# MSXII_SteeringWheelLeftBoard.net
KiCad netlist of a schematic drawn in Altium Designer
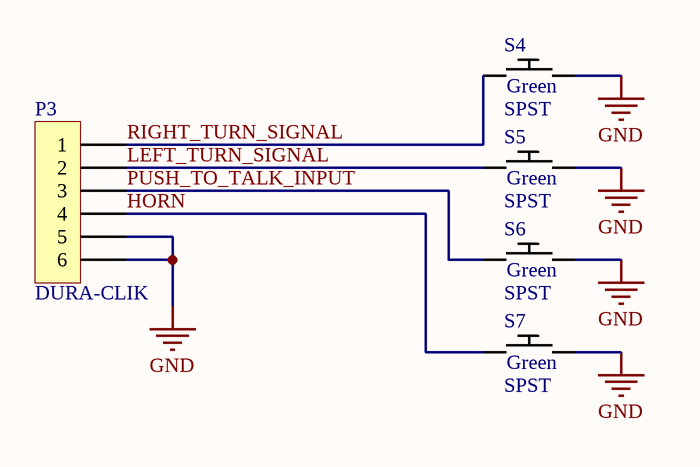
[diagram p0: MSXII_SteeringWheelLeftBoard.SchDoc]

(export (version "E")
  (design (tool "Eeschema 10.0.6"))
  (components
    (comp (ref "P3")
      (value "DURA-CLIK")
      (footprint "CONN, 6POS DURA-CLIK VERT")
      (description "6 Positions Header, Shrouded Connector 0.079\" (2.00mm) Surface Mount, Vertical Tin")
      (fields (field (name "MANUFACTURER") "Molex") (field (name "MANUFACTURER PART NUMBER") "5600200820"))
      (libsource (lib "Schematic Diagrams") (part "CONN 6POS DURA-CLIK 0.079{dblquote}"))
    )
    (comp (ref "S4")
      (value "SPST")
      (footprint "SW SPST D6 SERIES GREEN")
      (description "Pushbutton Switch SPST-NO Keyswitch Through Hole D6 Series Green")
      (fields (field (name "MANUFACTURER") "C&K") (field (name "MANUFACTURER PART NUMBER") "D6R50 F1 LFS"))
      (libsource (lib "Schematic Diagrams") (part "SW SPST-NO 0.1A 32V D6 Series Green"))
    )
    (comp (ref "S5")
      (value "SPST")
      (footprint "SW SPST D6 SERIES GREEN")
      (description "Pushbutton Switch SPST-NO Keyswitch Through Hole D6 Series Green")
      (fields (field (name "MANUFACTURER") "C&K") (field (name "MANUFACTURER PART NUMBER") "D6R50 F1 LFS"))
      (libsource (lib "Schematic Diagrams") (part "SW SPST-NO 0.1A 32V D6 Series Green"))
    )
    (comp (ref "S6")
      (value "SPST")
      (footprint "SW SPST D6 SERIES GREEN")
      (description "Pushbutton Switch SPST-NO Keyswitch Through Hole D6 Series Green")
      (fields (field (name "MANUFACTURER") "C&K") (field (name "MANUFACTURER PART NUMBER") "D6R50 F1 LFS"))
      (libsource (lib "Schematic Diagrams") (part "SW SPST-NO 0.1A 32V D6 Series Green"))
    )
    (comp (ref "S7")
      (value "SPST")
      (footprint "SW SPST D6 SERIES GREEN")
      (description "Pushbutton Switch SPST-NO Keyswitch Through Hole D6 Series Green")
      (fields (field (name "MANUFACTURER") "C&K") (field (name "MANUFACTURER PART NUMBER") "D6R50 F1 LFS"))
      (libsource (lib "Schematic Diagrams") (part "SW SPST-NO 0.1A 32V D6 Series Green"))
    )
  )
  (nets
    (net (code "1") (name "/HORN") (class "Default")
      (node (ref "P3") (pin "4") (pinfunction "4_4") (pintype "passive"))
      (node (ref "S7") (pin "1") (pinfunction "1_1") (pintype "passive"))
    )
    (net (code "2") (name "/LEFT_TURN_SIGNAL") (class "Default")
      (node (ref "P3") (pin "2") (pinfunction "2_2") (pintype "passive"))
      (node (ref "S5") (pin "1") (pinfunction "1_1") (pintype "passive"))
    )
    (net (code "3") (name "/PUSH_TO_TALK_INPUT") (class "Default")
      (node (ref "P3") (pin "3") (pinfunction "3_3") (pintype "passive"))
      (node (ref "S6") (pin "1") (pinfunction "1_1") (pintype "passive"))
    )
    (net (code "4") (name "/RIGHT_TURN_SIGNAL") (class "Default")
      (node (ref "P3") (pin "1") (pinfunction "1_1") (pintype "passive"))
      (node (ref "S4") (pin "1") (pinfunction "1_1") (pintype "passive"))
    )
    (net (code "5") (name "GND") (class "Default")
      (node (ref "P3") (pin "5") (pinfunction "5_5") (pintype "passive"))
      (node (ref "P3") (pin "6") (pinfunction "6_6") (pintype "passive"))
      (node (ref "S4") (pin "2") (pinfunction "2_2") (pintype "passive"))
      (node (ref "S5") (pin "2") (pinfunction "2_2") (pintype "passive"))
      (node (ref "S6") (pin "2") (pinfunction "2_2") (pintype "passive"))
      (node (ref "S7") (pin "2") (pinfunction "2_2") (pintype "passive"))
    )
  )
)
